# Digital_Sensor_Module.net
KiCad netlist of a schematic drawn in Altium Designer
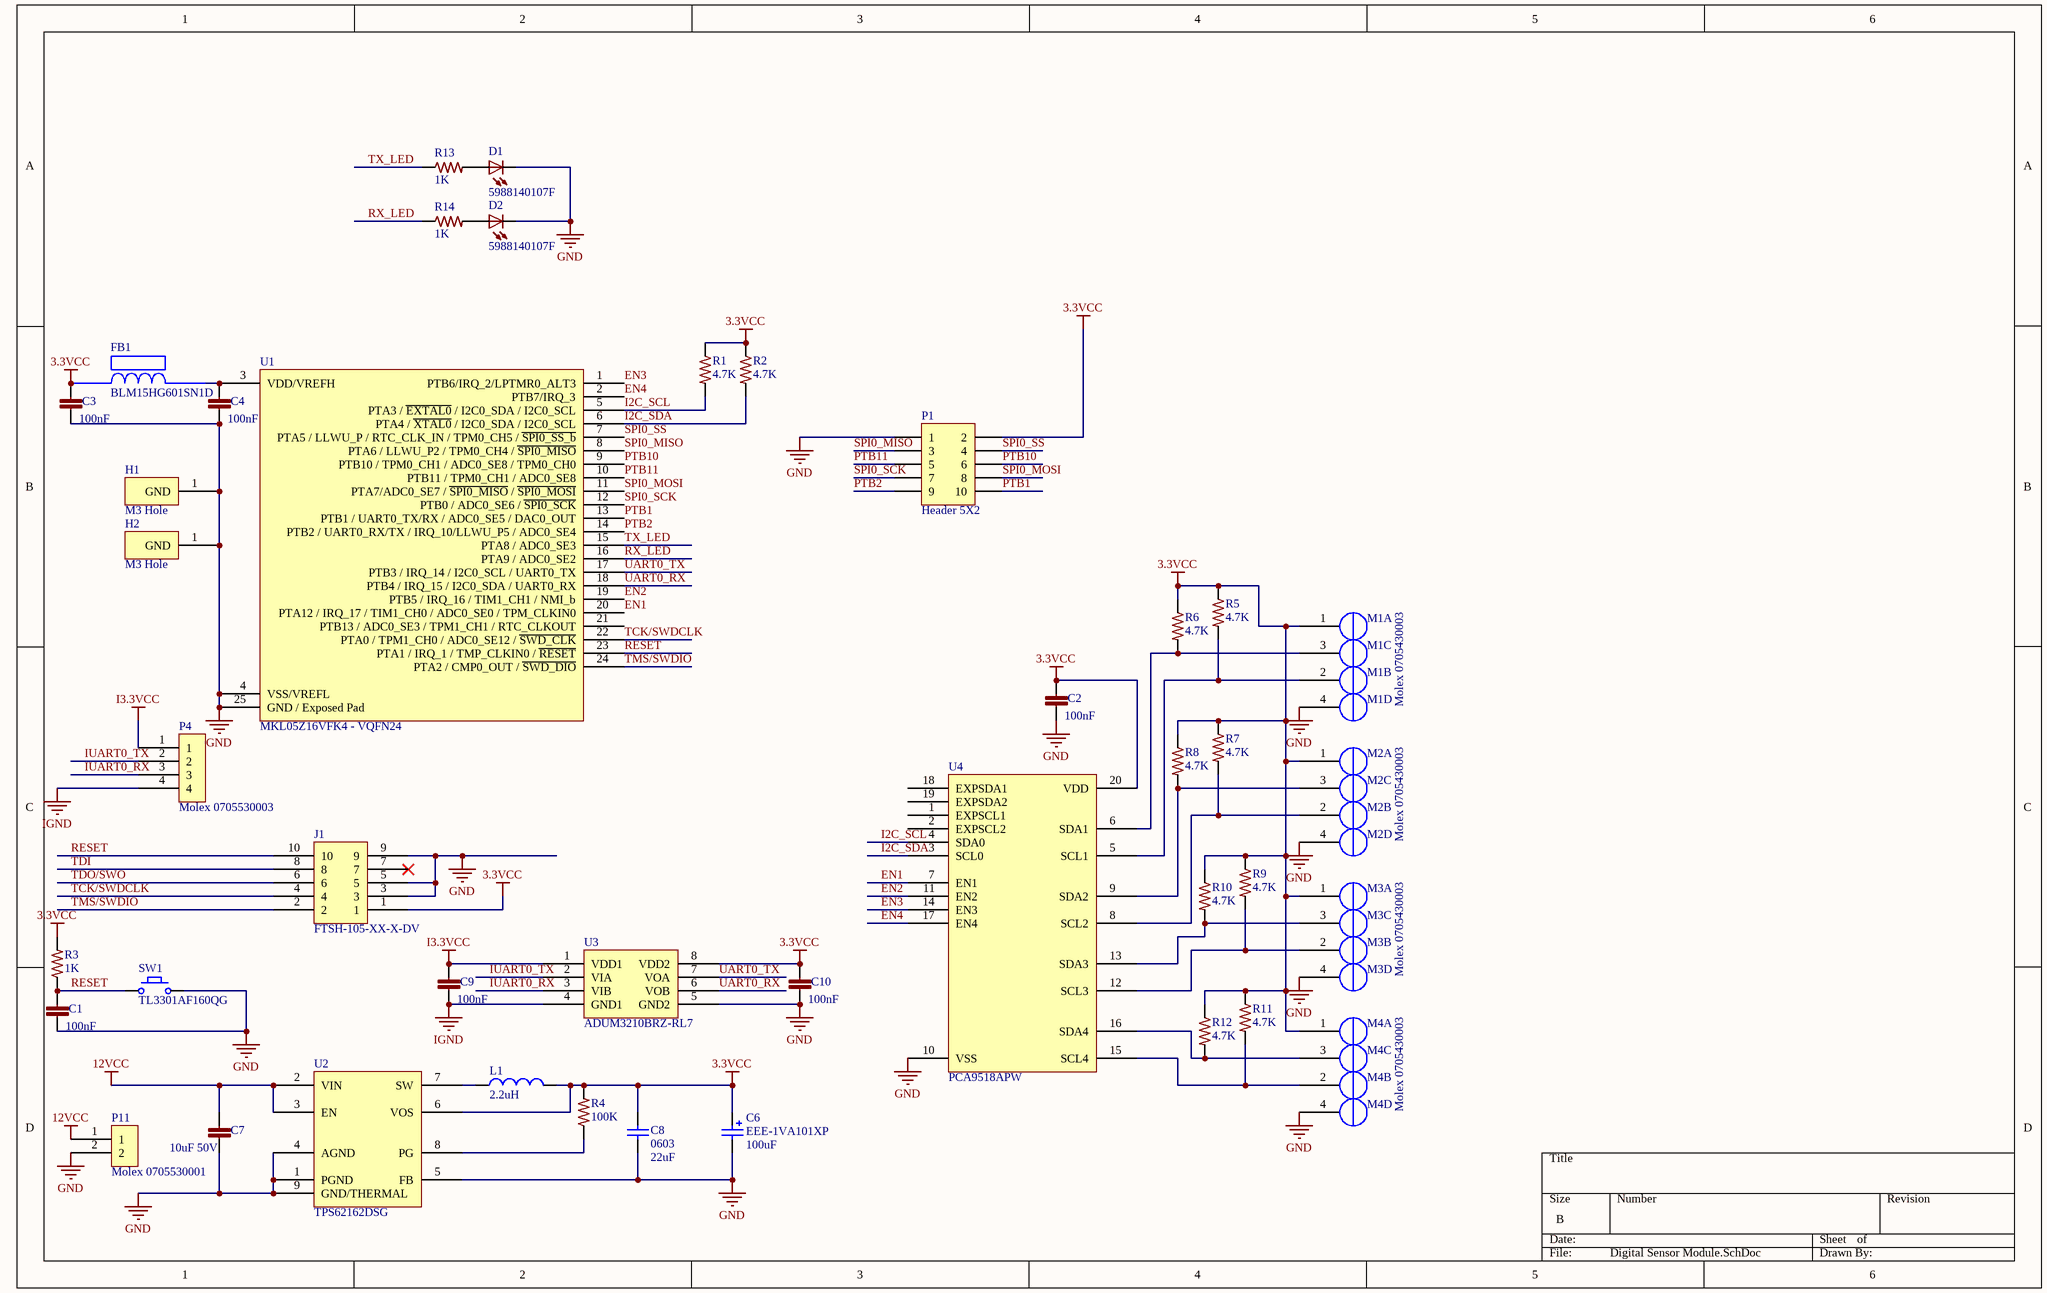
[diagram p0: Digital Sensor Module.SchDoc]

(export (version "E")
  (design (tool "Eeschema 10.0.6"))
  (components
    (comp (ref "C1")
      (value "100nF")
      (footprint "C0402")
      (description "CAP CER 0402 100nF 16V 10% X7R")
      (fields
        (field (name "MANUFACTURERPARTNUMBER") "GRM155R71C104KA88D")
        (field (name "PUBLISHER") "UltiMachine")
      )
      (libsource (lib "3Delight") (part "GRM155R71C104KA88D"))
    )
    (comp (ref "C2")
      (value "100nF")
      (footprint "C0402")
      (description "CAP CER 0402 100nF 16V 10% X7R")
      (fields
        (field (name "MANUFACTURERPARTNUMBER") "GRM155R71C104KA88D")
        (field (name "PUBLISHER") "UltiMachine")
      )
      (libsource (lib "3Delight") (part "GRM155R71C104KA88D"))
    )
    (comp (ref "C3")
      (value "100nF")
      (footprint "C0402")
      (description "CAP CER 0402 100nF 16V 10% X7R")
      (fields
        (field (name "MANUFACTURERPARTNUMBER") "GRM155R71C104KA88D")
        (field (name "PUBLISHER") "UltiMachine")
      )
      (libsource (lib "3Delight") (part "GRM155R71C104KA88D"))
    )
    (comp (ref "C4")
      (value "100nF")
      (footprint "C0402")
      (description "CAP CER 0402 100nF 16V 10% X7R")
      (fields
        (field (name "MANUFACTURERPARTNUMBER") "GRM155R71C104KA88D")
        (field (name "PUBLISHER") "UltiMachine")
      )
      (libsource (lib "3Delight") (part "GRM155R71C104KA88D"))
    )
    (comp (ref "C6")
      (value "EEE-1VA101XP")
      (footprint "EEE-1VA101XP")
      (description "CAP ALUM 100UF 35V 20% SMD")
      (fields (field (name "DIGIKEY PART #") "PCE3951CT-ND") (field (name "ALTIUM_VALUE") "100uF"))
      (libsource (lib "Tigershark3D") (part "EEE-1VA101XP"))
    )
    (comp (ref "C7")
      (value "10uF 50V")
      (footprint "C1206")
      (description "CAP CER 10UF 50V 10% X5R 1206")
      (fields
        (field (name "MANUFACTURER") "Samsung")
        (field (name "MANUFACTURERPARTNUMBER") "CL31A106KBHNNNE")
        (field (name "PUBLISHER") "UltiMachine")
      )
      (libsource (lib "Tigershark3D") (part "CL31A106KBHNNNE"))
    )
    (comp (ref "C8")
      (value "0603")
      (footprint "C0805")
      (description "CAP CER 22UF 6.3V 10% X5R 0805")
      (fields
        (field (name "MFR PART #") "CL21A226KQQNNNE")
        (field (name "MFR") "Samsung")
        (field (name "ALTIUM_VALUE") "22uF")
      )
      (libsource (lib "Sensor Package") (part "CL21A226KQQNNNE"))
    )
    (comp (ref "C9")
      (value "100nF")
      (footprint "C0402")
      (description "CAP CER 0402 100nF 16V 10% X7R")
      (fields
        (field (name "MANUFACTURERPARTNUMBER") "GRM155R71C104KA88D")
        (field (name "PUBLISHER") "UltiMachine")
      )
      (libsource (lib "3Delight") (part "GRM155R71C104KA88D"))
    )
    (comp (ref "C10")
      (value "100nF")
      (footprint "C0402")
      (description "CAP CER 0402 100nF 16V 10% X7R")
      (fields
        (field (name "MANUFACTURERPARTNUMBER") "GRM155R71C104KA88D")
        (field (name "PUBLISHER") "UltiMachine")
      )
      (libsource (lib "3Delight") (part "GRM155R71C104KA88D"))
    )
    (comp (ref "D1")
      (value "5988140107F")
      (footprint "LED2012120")
      (description "LED 0805 Yellow")
      (fields (field (name "PUBLISHER") "UltiMachine"))
      (libsource (lib "Tigershark3D") (part "5988140107F"))
    )
    (comp (ref "D2")
      (value "5988140107F")
      (footprint "LED2012120")
      (description "LED 0805 Yellow")
      (fields (field (name "PUBLISHER") "UltiMachine"))
      (libsource (lib "Tigershark3D") (part "5988140107F"))
    )
    (comp (ref "FB1")
      (value "BLM15HG601SN1D")
      (footprint "BLM18PG121SN1D")
      (libsource (lib "AHD Part Library") (part "BLM15HG601SN1D"))
    )
    (comp (ref "H1")
      (value "M3 Hole")
      (footprint "Hole-3mm")
      (description "3mm Hole")
      (libsource (lib "Sensor Package") (part "Hole"))
    )
    (comp (ref "H2")
      (value "M3 Hole")
      (footprint "Hole-3mm")
      (description "3mm Hole")
      (libsource (lib "Sensor Package") (part "Hole"))
    )
    (comp (ref "J1")
      (value "FTSH-105-XX-X-DV")
      (footprint "FTSH-105-XX-X-DV")
      (libsource (lib "Adams Altium Library") (part "ARM Cortex JTAG-DEBUG Header"))
    )
    (comp (ref "L1")
      (value "2.2uH")
      (footprint "VLS252012T-2R2M1R3")
      (description "VLS252012T-2R2M1R3")
      (fields (field (name "MFR") "TDK Corporation") (field (name "PUBLISHER") "Adam Vadala-Roth"))
      (libsource (lib "Sensor Package") (part "VLS252012T-2R2M1R3"))
    )
    (comp (ref "M1")
      (value "Molex 0705430003")
      (footprint "4POL254")
      (description "Molex 4 Pin Clip Connector")
      (libsource (lib "ZMBo Schematic Library") (part "Molex 0705430003 Alt"))
    )
    (comp (ref "M2")
      (value "Molex 0705430003")
      (footprint "4POL254")
      (description "Molex 4 Pin Clip Connector")
      (libsource (lib "ZMBo Schematic Library") (part "Molex 0705430003 Alt"))
    )
    (comp (ref "M3")
      (value "Molex 0705430003")
      (footprint "4POL254")
      (description "Molex 4 Pin Clip Connector")
      (libsource (lib "ZMBo Schematic Library") (part "Molex 0705430003 Alt"))
    )
    (comp (ref "M4")
      (value "Molex 0705430003")
      (footprint "4POL254")
      (description "Molex 4 Pin Clip Connector")
      (libsource (lib "ZMBo Schematic Library") (part "Molex 0705430003 Alt"))
    )
    (comp (ref "P1")
      (value "Header 5X2")
      (footprint "HDR2X5")
      (description "Header, 5-Pin, Dual row")
      (fields (field (name "PUBLISHER") "Altium Limited"))
      (libsource (lib "Miscellaneous Connectors") (part "Header 5X2"))
    )
    (comp (ref "P4")
      (value "Molex 0705530003")
      (footprint "0705530003")
      (description "Molex 0705530003 Right Angle 2.54mm Shrouded Header")
      (fields (field (name "MFR") "Molex"))
      (libsource (lib "Sensor Package") (part "0705530003"))
    )
    (comp (ref "P11")
      (value "Molex 0705530001")
      (footprint "0705530001")
      (description "Molex 0705530002 Right Angle 2.54mm Shrouded Header")
      (fields (field (name "MFR") "Molex"))
      (libsource (lib "Sensor Package") (part "0705530001"))
    )
    (comp (ref "R1")
      (value "4.7K")
      (footprint "R0603")
      (description "RES 0603 4.7K 100mW 1%")
      (fields (field (name "MANUFACTURERPARTNUMBER") "ERJ3EKF4701V") (field (name "PUBLISHER") "UltiMachine"))
      (libsource (lib "Tigershark3D") (part "ERJ3EKF4701V"))
    )
    (comp (ref "R2")
      (value "4.7K")
      (footprint "R0603")
      (description "RES 0603 4.7K 100mW 1%")
      (fields (field (name "MANUFACTURERPARTNUMBER") "ERJ3EKF4701V") (field (name "PUBLISHER") "UltiMachine"))
      (libsource (lib "Tigershark3D") (part "ERJ3EKF4701V"))
    )
    (comp (ref "R3")
      (value "1K")
      (footprint "R0603")
      (description "RES 0603 1K 100mW 1%")
      (fields
        (field (name "MANUFACTURERPARTNUMBER") "ERJ-3EKF1001V")
        (field (name "PUBLISHER") "UltiMachine")
      )
      (libsource (lib "3Delight") (part "ERJ-3EKF1001V"))
    )
    (comp (ref "R4")
      (value "100K")
      (footprint "R0603")
      (description "RES 100K OHM 1/10W 1% 0603 SMD")
      (fields
        (field (name "MANUFACTURERPARTNUMBER") "RC0603FR-07100KL")
        (field (name "PUBLISHER") "UltiMachine")
      )
      (libsource (lib "3Delight") (part "RC0603FR-07100KL"))
    )
    (comp (ref "R5")
      (value "4.7K")
      (footprint "R0603")
      (description "RES 0603 4.7K 100mW 1%")
      (fields (field (name "MANUFACTURERPARTNUMBER") "ERJ3EKF4701V") (field (name "PUBLISHER") "UltiMachine"))
      (libsource (lib "Tigershark3D") (part "ERJ3EKF4701V"))
    )
    (comp (ref "R6")
      (value "4.7K")
      (footprint "R0603")
      (description "RES 0603 4.7K 100mW 1%")
      (fields (field (name "MANUFACTURERPARTNUMBER") "ERJ3EKF4701V") (field (name "PUBLISHER") "UltiMachine"))
      (libsource (lib "Tigershark3D") (part "ERJ3EKF4701V"))
    )
    (comp (ref "R7")
      (value "4.7K")
      (footprint "R0603")
      (description "RES 0603 4.7K 100mW 1%")
      (fields (field (name "MANUFACTURERPARTNUMBER") "ERJ3EKF4701V") (field (name "PUBLISHER") "UltiMachine"))
      (libsource (lib "Tigershark3D") (part "ERJ3EKF4701V"))
    )
    (comp (ref "R8")
      (value "4.7K")
      (footprint "R0603")
      (description "RES 0603 4.7K 100mW 1%")
      (fields (field (name "MANUFACTURERPARTNUMBER") "ERJ3EKF4701V") (field (name "PUBLISHER") "UltiMachine"))
      (libsource (lib "Tigershark3D") (part "ERJ3EKF4701V"))
    )
    (comp (ref "R9")
      (value "4.7K")
      (footprint "R0603")
      (description "RES 0603 4.7K 100mW 1%")
      (fields (field (name "MANUFACTURERPARTNUMBER") "ERJ3EKF4701V") (field (name "PUBLISHER") "UltiMachine"))
      (libsource (lib "Tigershark3D") (part "ERJ3EKF4701V"))
    )
    (comp (ref "R10")
      (value "4.7K")
      (footprint "R0603")
      (description "RES 0603 4.7K 100mW 1%")
      (fields (field (name "MANUFACTURERPARTNUMBER") "ERJ3EKF4701V") (field (name "PUBLISHER") "UltiMachine"))
      (libsource (lib "Tigershark3D") (part "ERJ3EKF4701V"))
    )
    (comp (ref "R11")
      (value "4.7K")
      (footprint "R0603")
      (description "RES 0603 4.7K 100mW 1%")
      (fields (field (name "MANUFACTURERPARTNUMBER") "ERJ3EKF4701V") (field (name "PUBLISHER") "UltiMachine"))
      (libsource (lib "Tigershark3D") (part "ERJ3EKF4701V"))
    )
    (comp (ref "R12")
      (value "4.7K")
      (footprint "R0603")
      (description "RES 0603 4.7K 100mW 1%")
      (fields (field (name "MANUFACTURERPARTNUMBER") "ERJ3EKF4701V") (field (name "PUBLISHER") "UltiMachine"))
      (libsource (lib "Tigershark3D") (part "ERJ3EKF4701V"))
    )
    (comp (ref "R13")
      (value "1K")
      (footprint "R0603")
      (description "RES 0603 1K 100mW 1%")
      (fields
        (field (name "MANUFACTURERPARTNUMBER") "ERJ-3EKF1001V")
        (field (name "PUBLISHER") "UltiMachine")
      )
      (libsource (lib "Tigershark3D") (part "ERJ-3EKF1001V"))
    )
    (comp (ref "R14")
      (value "1K")
      (footprint "R0603")
      (description "RES 0603 1K 100mW 1%")
      (fields
        (field (name "MANUFACTURERPARTNUMBER") "ERJ-3EKF1001V")
        (field (name "PUBLISHER") "UltiMachine")
      )
      (libsource (lib "Tigershark3D") (part "ERJ-3EKF1001V"))
    )
    (comp (ref "SW1")
      (value "TL3301AF160QG")
      (footprint "TL3301AF160QG")
      (libsource (lib "MongoosMini") (part "TL3301AF160QG"))
    )
    (comp (ref "U1")
      (value "MKL05Z16VFK4 - VQFN24")
      (footprint "98ASA00474D")
      (description "ARM Cortex M0+")
      (libsource (lib "Encoder Fin") (part "MKL05Z16VFK4 - 24 Pin VQFN"))
    )
    (comp (ref "U2")
      (value "TPS62162DSG")
      (footprint "DSG8-1600X900TP")
      (libsource (lib "Adams Altium Library") (part "TPS62162SOP"))
    )
    (comp (ref "U3")
      (value "ADUM3210BRZ-RL7")
      (footprint "ADUM3210BRZ-RL7")
      (description "DGTL ISO 2.5KV GEN PURP 8SOIC")
      (fields (field (name "MFR") "Analog Devices"))
      (libsource (lib "Sensor Package") (part "ADUM3210BRZ-RL7"))
    )
    (comp (ref "U4")
      (value "PCA9518APW")
      (footprint "PCA9518APW,512")
      (description "IC I2C HUB 5CH EXPANDBL 20-TSSOP")
      (fields (field (name "MFR") "NXP"))
      (libsource (lib "Sensor Package") (part "PCA9518APW512"))
    )
  )
  (nets
    (net (code "1") (name "/EN1") (class "Default")
      (node (ref "U1") (pin "20") (pinfunction "PTA12_/_IRQ_17_/_TIM1_CH0_/_ADC0_SE0_/_TPM_CLKIN0_20") (pintype "passive"))
      (node (ref "U4") (pin "7") (pinfunction "EN1_7") (pintype "passive"))
    )
    (net (code "2") (name "/EN2") (class "Default")
      (node (ref "U1") (pin "19") (pinfunction "PTB5_/_IRQ_16_/_TIM1_CH1_/_NMI_b_19") (pintype "passive"))
      (node (ref "U4") (pin "11") (pinfunction "EN2_11") (pintype "passive"))
    )
    (net (code "3") (name "/EN3") (class "Default")
      (node (ref "U1") (pin "1") (pinfunction "PTB6/IRQ_2/LPTMR0_ALT3_1") (pintype "passive"))
      (node (ref "U4") (pin "14") (pinfunction "EN3_14") (pintype "passive"))
    )
    (net (code "4") (name "/EN4") (class "Default")
      (node (ref "U1") (pin "2") (pinfunction "PTB7/IRQ_3_2") (pintype "passive"))
      (node (ref "U4") (pin "17") (pinfunction "EN4_17") (pintype "passive"))
    )
    (net (code "5") (name "/I2C_SCL") (class "Default")
      (node (ref "R1") (pin "2") (pinfunction "2_2") (pintype "passive"))
      (node (ref "U1") (pin "5") (pinfunction "PTA3_/_~{EXTAL0}_/_I2C0_SDA_/_I2C0_SCL_5") (pintype "passive"))
      (node (ref "U4") (pin "4") (pinfunction "SDA0_4") (pintype "passive"))
    )
    (net (code "6") (name "/I2C_SDA") (class "Default")
      (node (ref "R2") (pin "2") (pinfunction "2_2") (pintype "passive"))
      (node (ref "U1") (pin "6") (pinfunction "PTA4_/_~{XTAL0}_/_I2C0_SDA_/_I2C0_SCL_6") (pintype "passive"))
      (node (ref "U4") (pin "3") (pinfunction "SCL0_3") (pintype "passive"))
    )
    (net (code "7") (name "/IUART0_RX") (class "Default")
      (node (ref "P4") (pin "3") (pinfunction "3_3") (pintype "passive"))
      (node (ref "U3") (pin "3") (pinfunction "VIB_3") (pintype "passive"))
    )
    (net (code "8") (name "/IUART0_TX") (class "Default")
      (node (ref "P4") (pin "2") (pinfunction "2_2") (pintype "passive"))
      (node (ref "U3") (pin "2") (pinfunction "VIA_2") (pintype "passive"))
    )
    (net (code "9") (name "/PTB1") (class "Default")
      (node (ref "P1") (pin "10") (pinfunction "10_10") (pintype "passive"))
      (node (ref "U1") (pin "13") (pinfunction "PTB1_/_UART0_TX/RX_/_ADC0_SE5_/_DAC0_OUT_13") (pintype "passive"))
    )
    (net (code "10") (name "/PTB2") (class "Default")
      (node (ref "P1") (pin "9") (pinfunction "9_9") (pintype "passive"))
      (node (ref "U1") (pin "14") (pinfunction "PTB2_/_UART0_RX/TX_/_IRQ_10/LLWU_P5_/_ADC0_SE4_14") (pintype "passive"))
    )
    (net (code "11") (name "/PTB10") (class "Default")
      (node (ref "P1") (pin "6") (pinfunction "6_6") (pintype "passive"))
      (node (ref "U1") (pin "9") (pinfunction "PTB10_/_TPM0_CH1_/_ADC0_SE8_/_TPM0_CH0_9") (pintype "passive"))
    )
    (net (code "12") (name "/PTB11") (class "Default")
      (node (ref "P1") (pin "5") (pinfunction "5_5") (pintype "passive"))
      (node (ref "U1") (pin "10") (pinfunction "PTB11_/_TPM0_CH1_/_ADC0_SE8_10") (pintype "passive"))
    )
    (net (code "13") (name "/RESET") (class "Default")
      (node (ref "C1") (pin "1") (pinfunction "1_1") (pintype "passive"))
      (node (ref "J1") (pin "10") (pinfunction "10_10") (pintype "passive"))
      (node (ref "R3") (pin "1") (pinfunction "1_1") (pintype "passive"))
      (node (ref "SW1") (pin "1") (pintype "passive"))
      (node (ref "U1") (pin "23") (pinfunction "PTA1_/_IRQ_1_/_TMP_CLKIN0_/_~{RESET}_23") (pintype "passive"))
    )
    (net (code "14") (name "/RX_LED") (class "Default")
      (node (ref "R14") (pin "1") (pinfunction "1_1") (pintype "passive"))
      (node (ref "U1") (pin "16") (pinfunction "PTA9_/_ADC0_SE2_16") (pintype "passive"))
    )
    (net (code "15") (name "/SPI0_MISO") (class "Default")
      (node (ref "P1") (pin "3") (pinfunction "3_3") (pintype "passive"))
      (node (ref "U1") (pin "8") (pinfunction "PTA6_/_LLWU_P2_/_TPM0_CH4_/_~{SPI0_MISO}_8") (pintype "passive"))
    )
    (net (code "16") (name "/SPI0_MOSI") (class "Default")
      (node (ref "P1") (pin "8") (pinfunction "8_8") (pintype "passive"))
      (node (ref "U1") (pin "11") (pinfunction "PTA7/ADC0_SE7_/_~{SPI0_MISO}_/_~{SPI0_MOSI}_11") (pintype "passive"))
    )
    (net (code "17") (name "/SPI0_SCK") (class "Default")
      (node (ref "P1") (pin "7") (pinfunction "7_7") (pintype "passive"))
      (node (ref "U1") (pin "12") (pinfunction "PTB0_/_ADC0_SE6_/_~{SPI0_SCK}_12") (pintype "passive"))
    )
    (net (code "18") (name "/SPI0_SS") (class "Default")
      (node (ref "P1") (pin "4") (pinfunction "4_4") (pintype "passive"))
      (node (ref "U1") (pin "7") (pinfunction "PTA5_/_LLWU_P_/_RTC_CLK_IN_/_TPM0_CH5_/_~{SPI0_SS_b}_7") (pintype "passive"))
    )
    (net (code "19") (name "/TCK{slash}SWDCLK") (class "Default")
      (node (ref "J1") (pin "4") (pinfunction "4_4") (pintype "passive"))
      (node (ref "U1") (pin "22") (pinfunction "PTA0_/_TPM1_CH0_/_ADC0_SE12_/_~{SWD_CLK}_22") (pintype "passive"))
    )
    (net (code "20") (name "/TDI") (class "Default")
      (node (ref "J1") (pin "8") (pinfunction "8_8") (pintype "passive"))
    )
    (net (code "21") (name "/TDO{slash}SWO") (class "Default")
      (node (ref "J1") (pin "6") (pinfunction "6_6") (pintype "passive"))
    )
    (net (code "22") (name "/TMS{slash}SWDIO") (class "Default")
      (node (ref "J1") (pin "2") (pinfunction "2_2") (pintype "passive"))
      (node (ref "U1") (pin "24") (pinfunction "PTA2_/_CMP0_OUT_/_~{SWD_DIO}_24") (pintype "passive"))
    )
    (net (code "23") (name "/TX_LED") (class "Default")
      (node (ref "R13") (pin "1") (pinfunction "1_1") (pintype "passive"))
      (node (ref "U1") (pin "15") (pinfunction "PTA8_/_ADC0_SE3_15") (pintype "passive"))
    )
    (net (code "24") (name "/UART0_RX") (class "Default")
      (node (ref "U1") (pin "18") (pinfunction "PTB4_/_IRQ_15_/_I2C0_SDA_/_UART0_RX_18") (pintype "passive"))
      (node (ref "U3") (pin "6") (pinfunction "VOB_6") (pintype "passive"))
    )
    (net (code "25") (name "/UART0_TX") (class "Default")
      (node (ref "U1") (pin "17") (pinfunction "PTB3_/_IRQ_14_/_I2C0_SCL_/_UART0_TX_17") (pintype "passive"))
      (node (ref "U3") (pin "7") (pinfunction "VOA_7") (pintype "passive"))
    )
    (net (code "26") (name "3.3VCC") (class "Default")
      (node (ref "C10") (pin "1") (pinfunction "1_1") (pintype "passive"))
      (node (ref "C2") (pin "1") (pinfunction "1_1") (pintype "passive"))
      (node (ref "C3") (pin "1") (pinfunction "1_1") (pintype "passive"))
      (node (ref "C6") (pin "1") (pinfunction "1_1") (pintype "passive"))
      (node (ref "C8") (pin "2") (pinfunction "2_2") (pintype "passive"))
      (node (ref "FB1") (pin "1") (pinfunction "1_1") (pintype "passive"))
      (node (ref "J1") (pin "1") (pinfunction "1_1") (pintype "passive"))
      (node (ref "L1") (pin "2") (pinfunction "2_2") (pintype "passive"))
      (node (ref "M1") (pin "1") (pinfunction "OUT2B_1") (pintype "passive"))
      (node (ref "M2") (pin "1") (pinfunction "OUT2B_1") (pintype "passive"))
      (node (ref "M3") (pin "1") (pinfunction "OUT2B_1") (pintype "passive"))
      (node (ref "M4") (pin "1") (pinfunction "OUT2B_1") (pintype "passive"))
      (node (ref "P1") (pin "2") (pinfunction "2_2") (pintype "passive"))
      (node (ref "R1") (pin "1") (pinfunction "1_1") (pintype "passive"))
      (node (ref "R10") (pin "1") (pinfunction "1_1") (pintype "passive"))
      (node (ref "R11") (pin "1") (pinfunction "1_1") (pintype "passive"))
      (node (ref "R12") (pin "1") (pinfunction "1_1") (pintype "passive"))
      (node (ref "R2") (pin "1") (pinfunction "1_1") (pintype "passive"))
      (node (ref "R3") (pin "2") (pinfunction "2_2") (pintype "passive"))
      (node (ref "R4") (pin "2") (pinfunction "2_2") (pintype "passive"))
      (node (ref "R5") (pin "1") (pinfunction "1_1") (pintype "passive"))
      (node (ref "R6") (pin "1") (pinfunction "1_1") (pintype "passive"))
      (node (ref "R7") (pin "1") (pinfunction "1_1") (pintype "passive"))
      (node (ref "R8") (pin "1") (pinfunction "1_1") (pintype "passive"))
      (node (ref "R9") (pin "1") (pinfunction "1_1") (pintype "passive"))
      (node (ref "U2") (pin "6") (pinfunction "VOS_6") (pintype "passive"))
      (node (ref "U3") (pin "8") (pinfunction "VDD2_8") (pintype "passive"))
      (node (ref "U4") (pin "20") (pinfunction "VDD_20") (pintype "passive"))
    )
    (net (code "27") (name "12VCC") (class "Default")
      (node (ref "C7") (pin "1") (pinfunction "1_1") (pintype "passive"))
      (node (ref "P11") (pin "1") (pinfunction "1_1") (pintype "passive"))
      (node (ref "U2") (pin "2") (pinfunction "VIN_2") (pintype "passive"))
      (node (ref "U2") (pin "3") (pinfunction "EN_3") (pintype "passive"))
    )
    (net (code "28") (name "GND") (class "Default")
      (node (ref "C1") (pin "2") (pinfunction "2_2") (pintype "passive"))
      (node (ref "C10") (pin "2") (pinfunction "2_2") (pintype "passive"))
      (node (ref "C2") (pin "2") (pinfunction "2_2") (pintype "passive"))
      (node (ref "C3") (pin "2") (pinfunction "2_2") (pintype "passive"))
      (node (ref "C4") (pin "2") (pinfunction "2_2") (pintype "passive"))
      (node (ref "C6") (pin "2") (pinfunction "2_2") (pintype "passive"))
      (node (ref "C7") (pin "2") (pinfunction "2_2") (pintype "passive"))
      (node (ref "C8") (pin "1") (pinfunction "1_1") (pintype "passive"))
      (node (ref "D1") (pin "C") (pinfunction "C_C") (pintype "passive"))
      (node (ref "D2") (pin "C") (pinfunction "C_C") (pintype "passive"))
      (node (ref "H1") (pin "1") (pinfunction "GND_1") (pintype "passive"))
      (node (ref "H2") (pin "1") (pinfunction "GND_1") (pintype "passive"))
      (node (ref "J1") (pin "3") (pinfunction "3_3") (pintype "passive"))
      (node (ref "J1") (pin "5") (pinfunction "5_5") (pintype "passive"))
      (node (ref "J1") (pin "9") (pinfunction "9_9") (pintype "passive"))
      (node (ref "M1") (pin "4") (pinfunction "OUT1B_4") (pintype "passive"))
      (node (ref "M2") (pin "4") (pinfunction "OUT1B_4") (pintype "passive"))
      (node (ref "M3") (pin "4") (pinfunction "OUT1B_4") (pintype "passive"))
      (node (ref "M4") (pin "4") (pinfunction "OUT1B_4") (pintype "passive"))
      (node (ref "P1") (pin "1") (pinfunction "1_1") (pintype "passive"))
      (node (ref "P11") (pin "2") (pinfunction "2_2") (pintype "passive"))
      (node (ref "SW1") (pin "2") (pintype "passive"))
      (node (ref "U1") (pin "25") (pinfunction "GND_/_Exposed_Pad_25") (pintype "passive"))
      (node (ref "U1") (pin "4") (pinfunction "VSS/VREFL_4") (pintype "passive"))
      (node (ref "U2") (pin "1") (pinfunction "PGND_1") (pintype "passive"))
      (node (ref "U2") (pin "4") (pinfunction "AGND_4") (pintype "passive"))
      (node (ref "U2") (pin "5") (pinfunction "FB_5") (pintype "passive"))
      (node (ref "U2") (pin "9") (pinfunction "GND/THERMAL_9") (pintype "passive"))
      (node (ref "U3") (pin "5") (pinfunction "GND2_5") (pintype "passive"))
      (node (ref "U4") (pin "10") (pinfunction "VSS_10") (pintype "passive"))
    )
    (net (code "29") (name "I3.3VCC") (class "Default")
      (node (ref "C9") (pin "1") (pinfunction "1_1") (pintype "passive"))
      (node (ref "P4") (pin "1") (pinfunction "1_1") (pintype "passive"))
      (node (ref "U3") (pin "1") (pinfunction "VDD1_1") (pintype "passive"))
    )
    (net (code "30") (name "IGND") (class "Default")
      (node (ref "C9") (pin "2") (pinfunction "2_2") (pintype "passive"))
      (node (ref "P4") (pin "4") (pinfunction "4_4") (pintype "passive"))
      (node (ref "U3") (pin "4") (pinfunction "GND1_4") (pintype "passive"))
    )
    (net (code "31") (name "Net-(D1-PadA)") (class "Default")
      (node (ref "D1") (pin "A") (pinfunction "A_A") (pintype "passive"))
      (node (ref "R13") (pin "2") (pinfunction "2_2") (pintype "passive"))
    )
    (net (code "32") (name "Net-(D2-PadA)") (class "Default")
      (node (ref "D2") (pin "A") (pinfunction "A_A") (pintype "passive"))
      (node (ref "R14") (pin "2") (pinfunction "2_2") (pintype "passive"))
    )
    (net (code "33") (name "Net-(M1B-OUT2A)") (class "Default")
      (node (ref "M1") (pin "2") (pinfunction "OUT2A_2") (pintype "passive"))
      (node (ref "R5") (pin "2") (pinfunction "2_2") (pintype "passive"))
      (node (ref "U4") (pin "5") (pinfunction "SCL1_5") (pintype "passive"))
    )
    (net (code "34") (name "Net-(M1C-OUT1A)") (class "Default")
      (node (ref "M1") (pin "3") (pinfunction "OUT1A_3") (pintype "passive"))
      (node (ref "R6") (pin "2") (pinfunction "2_2") (pintype "passive"))
      (node (ref "U4") (pin "6") (pinfunction "SDA1_6") (pintype "passive"))
    )
    (net (code "35") (name "Net-(M2B-OUT2A)") (class "Default")
      (node (ref "M2") (pin "2") (pinfunction "OUT2A_2") (pintype "passive"))
      (node (ref "R7") (pin "2") (pinfunction "2_2") (pintype "passive"))
      (node (ref "U4") (pin "8") (pinfunction "SCL2_8") (pintype "passive"))
    )
    (net (code "36") (name "Net-(M2C-OUT1A)") (class "Default")
      (node (ref "M2") (pin "3") (pinfunction "OUT1A_3") (pintype "passive"))
      (node (ref "R8") (pin "2") (pinfunction "2_2") (pintype "passive"))
      (node (ref "U4") (pin "9") (pinfunction "SDA2_9") (pintype "passive"))
    )
    (net (code "37") (name "Net-(M3B-OUT2A)") (class "Default")
      (node (ref "M3") (pin "2") (pinfunction "OUT2A_2") (pintype "passive"))
      (node (ref "R9") (pin "2") (pinfunction "2_2") (pintype "passive"))
      (node (ref "U4") (pin "12") (pinfunction "SCL3_12") (pintype "passive"))
    )
    (net (code "38") (name "Net-(M3C-OUT1A)") (class "Default")
      (node (ref "M3") (pin "3") (pinfunction "OUT1A_3") (pintype "passive"))
      (node (ref "R10") (pin "2") (pinfunction "2_2") (pintype "passive"))
      (node (ref "U4") (pin "13") (pinfunction "SDA3_13") (pintype "passive"))
    )
    (net (code "39") (name "Net-(M4B-OUT2A)") (class "Default")
      (node (ref "M4") (pin "2") (pinfunction "OUT2A_2") (pintype "passive"))
      (node (ref "R11") (pin "2") (pinfunction "2_2") (pintype "passive"))
      (node (ref "U4") (pin "15") (pinfunction "SCL4_15") (pintype "passive"))
    )
    (net (code "40") (name "Net-(M4C-OUT1A)") (class "Default")
      (node (ref "M4") (pin "3") (pinfunction "OUT1A_3") (pintype "passive"))
      (node (ref "R12") (pin "2") (pinfunction "2_2") (pintype "passive"))
      (node (ref "U4") (pin "16") (pinfunction "SDA4_16") (pintype "passive"))
    )
    (net (code "41") (name "Net-(U1-VDD{slash}VREFH)") (class "Default")
      (node (ref "C4") (pin "1") (pinfunction "1_1") (pintype "passive"))
      (node (ref "FB1") (pin "2") (pinfunction "2_2") (pintype "passive"))
      (node (ref "U1") (pin "3") (pinfunction "VDD/VREFH_3") (pintype "passive"))
    )
    (net (code "42") (name "Net-(U2-PG)") (class "Default")
      (node (ref "R4") (pin "1") (pinfunction "1_1") (pintype "passive"))
      (node (ref "U2") (pin "8") (pinfunction "PG_8") (pintype "passive"))
    )
    (net (code "43") (name "Net-(U2-SW)") (class "Default")
      (node (ref "L1") (pin "1") (pinfunction "1_1") (pintype "passive"))
      (node (ref "U2") (pin "7") (pinfunction "SW_7") (pintype "passive"))
    )
    (net (code "44") (name "unconnected-(J1-Pad7)") (class "Default")
      (node (ref "J1") (pin "7") (pinfunction "7_7") (pintype "passive+no_connect"))
    )
    (net (code "45") (name "unconnected-(U1-PTB13_{slash}_ADC0_SE3_{slash}_TPM1_CH1_{slash}_RTC_CLKOUT-Pad21)") (class "Default")
      (node (ref "U1") (pin "21") (pinfunction "PTB13_/_ADC0_SE3_/_TPM1_CH1_/_RTC_CLKOUT_21") (pintype "passive"))
    )
    (net (code "46") (name "unconnected-(U4-EXPSCL1-Pad1)") (class "Default")
      (node (ref "U4") (pin "1") (pinfunction "EXPSCL1_1") (pintype "passive"))
    )
    (net (code "47") (name "unconnected-(U4-EXPSCL2-Pad2)") (class "Default")
      (node (ref "U4") (pin "2") (pinfunction "EXPSCL2_2") (pintype "passive"))
    )
    (net (code "48") (name "unconnected-(U4-EXPSDA1-Pad18)") (class "Default")
      (node (ref "U4") (pin "18") (pinfunction "EXPSDA1_18") (pintype "passive"))
    )
    (net (code "49") (name "unconnected-(U4-EXPSDA2-Pad19)") (class "Default")
      (node (ref "U4") (pin "19") (pinfunction "EXPSDA2_19") (pintype "passive"))
    )
  )
)
